# 150309_AriloRX_REV3_1_0.net
KiCad netlist of a schematic drawn in EAGLE
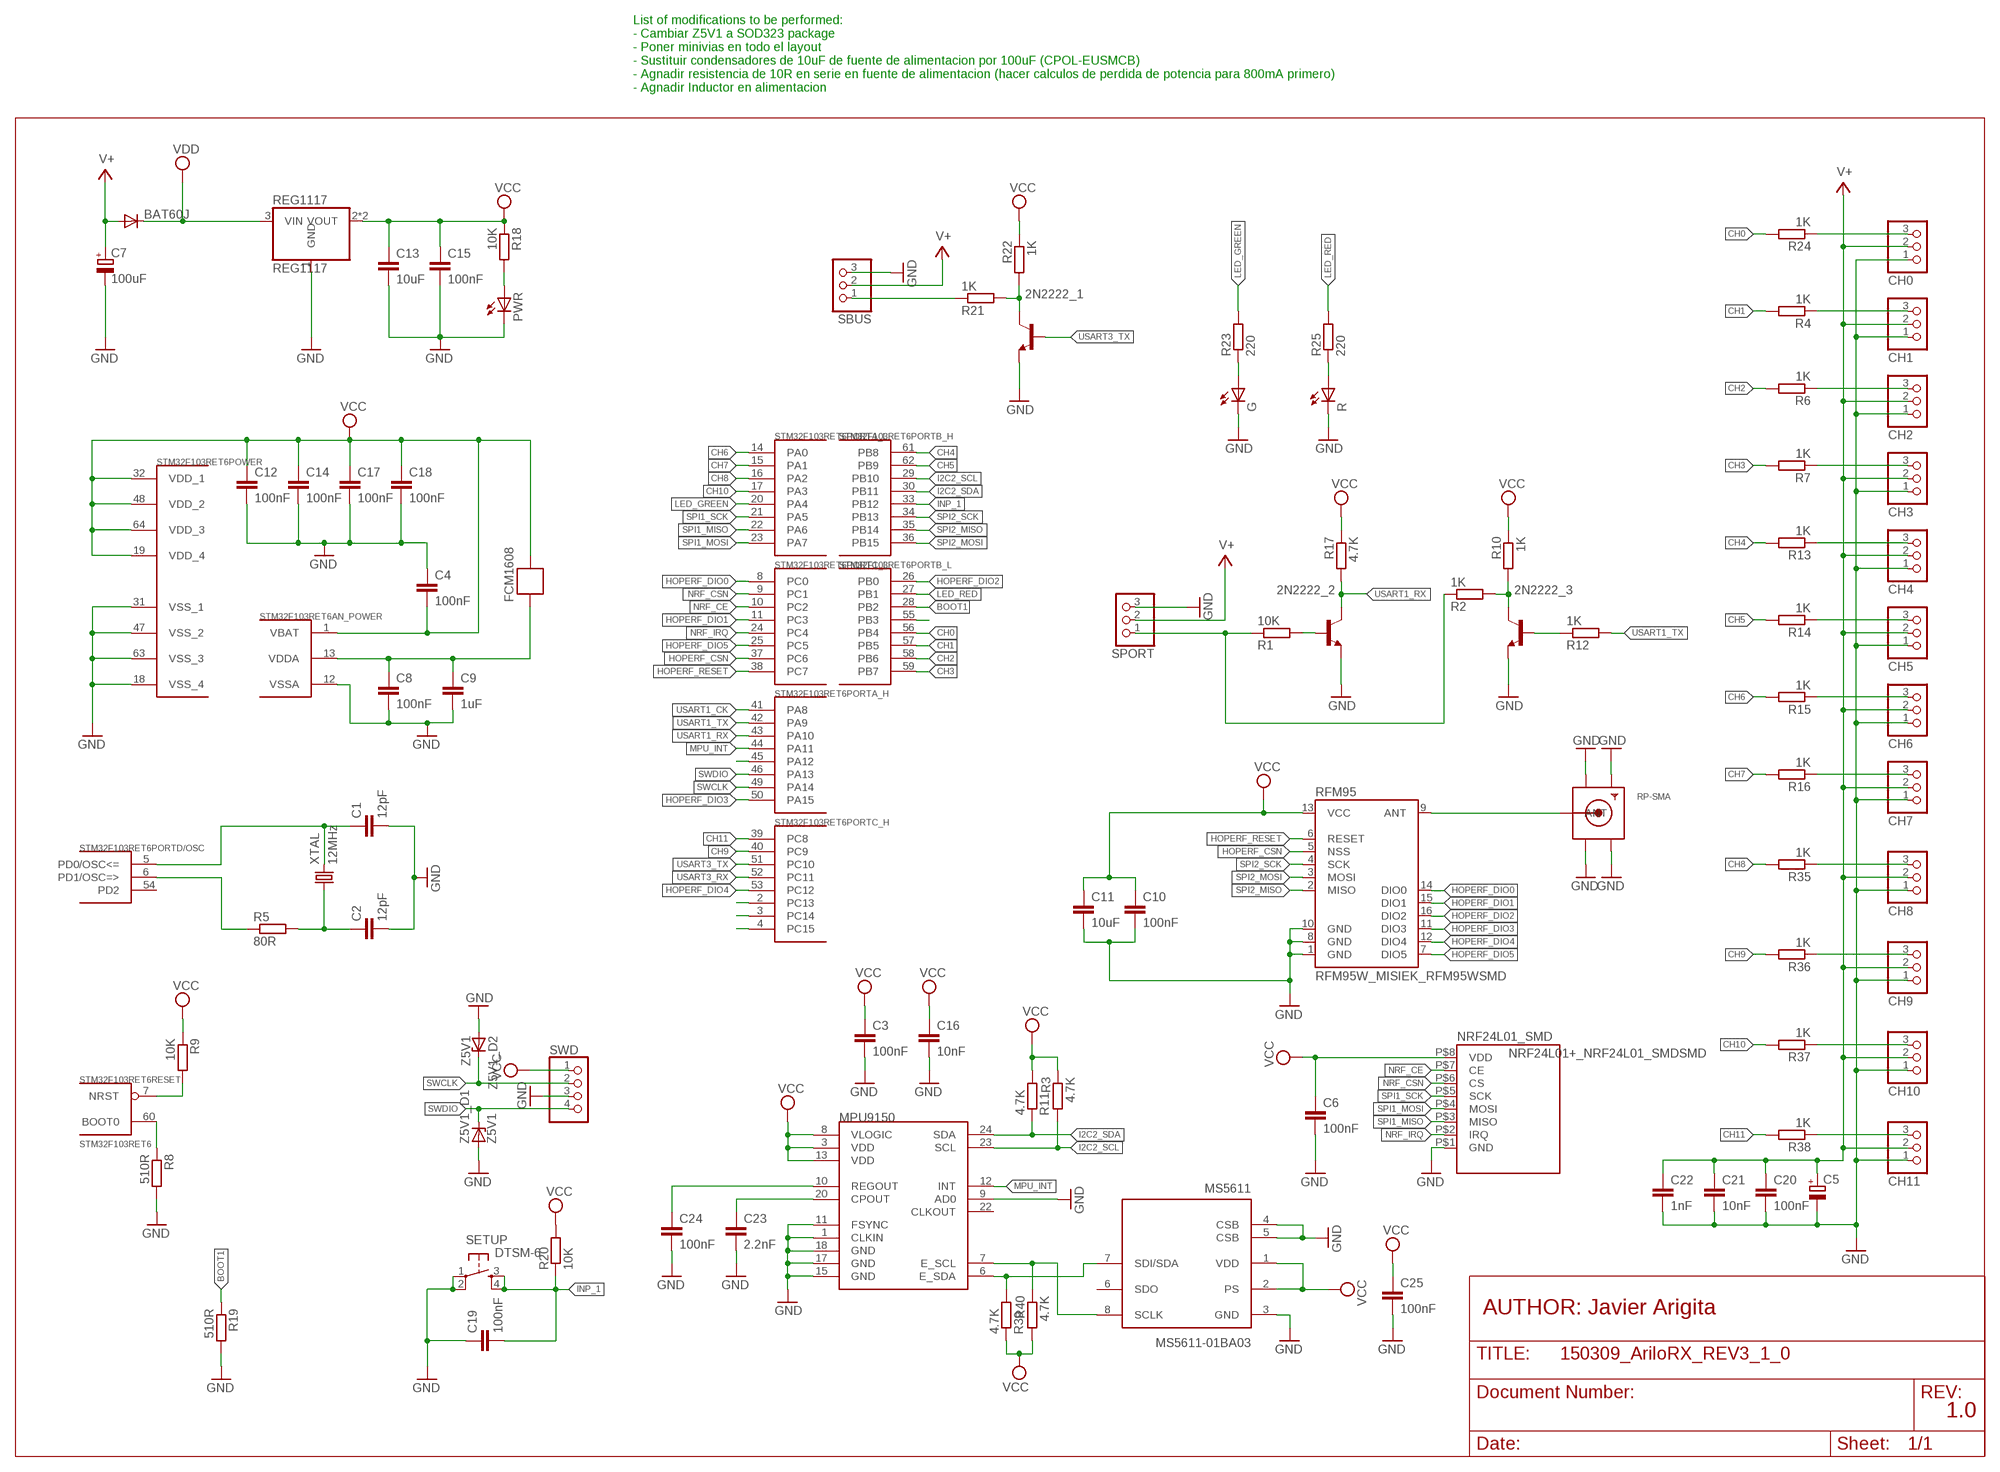
[diagram p0: schematic, sheet 1]

(export (version "E")
  (design (tool "Eeschema 10.0.6"))
  (components
    (comp (ref "2N2222_1")
      (value "MMBT2222ALT1-NPN-SOT23-BEC")
      (footprint "eagle-import:SOT23-BEC")
      (libsource (lib "eagle-import") (part "-NPN-SOT23-BECMMBT2222ALT1"))
    )
    (comp (ref "2N2222_2")
      (value "MMBT2222ALT1-NPN-SOT23-BEC")
      (footprint "eagle-import:SOT23-BEC")
      (libsource (lib "eagle-import") (part "-NPN-SOT23-BECMMBT2222ALT1"))
    )
    (comp (ref "2N2222_3")
      (value "MMBT2222ALT1-NPN-SOT23-BEC")
      (footprint "eagle-import:SOT23-BEC")
      (libsource (lib "eagle-import") (part "-NPN-SOT23-BECMMBT2222ALT1"))
    )
    (comp (ref "BAT60J")
      (value "DIODE-SOD323-R")
      (footprint "eagle-import:SOD323-R")
      (libsource (lib "eagle-import") (part "DIODE-SOD323-R"))
    )
    (comp (ref "C1")
      (value "12pF")
      (footprint "eagle-import:RESISTOR_C0603")
      (libsource (lib "eagle-import") (part "RESISTOR_C-EUC0603"))
    )
    (comp (ref "C2")
      (value "12pF")
      (footprint "eagle-import:RESISTOR_C0603")
      (libsource (lib "eagle-import") (part "RESISTOR_C-EUC0603"))
    )
    (comp (ref "C3")
      (value "100nF")
      (footprint "eagle-import:RESISTOR_C0603")
      (libsource (lib "eagle-import") (part "RESISTOR_C-EUC0603"))
    )
    (comp (ref "C4")
      (value "100nF")
      (footprint "eagle-import:RESISTOR_C0603")
      (libsource (lib "eagle-import") (part "RESISTOR_C-EUC0603"))
    )
    (comp (ref "C5")
      (value "CPOL-EUSMCB")
      (footprint "eagle-import:SMC_B")
      (libsource (lib "eagle-import") (part "CPOL-EUSMCB"))
    )
    (comp (ref "C6")
      (value "100nF")
      (footprint "eagle-import:RESISTOR_C0603")
      (libsource (lib "eagle-import") (part "RESISTOR_C-EUC0603"))
    )
    (comp (ref "C7")
      (value "100uF")
      (footprint "eagle-import:SMC_B")
      (libsource (lib "eagle-import") (part "CPOL-EUSMCB"))
    )
    (comp (ref "C8")
      (value "100nF")
      (footprint "eagle-import:RESISTOR_C0603")
      (libsource (lib "eagle-import") (part "RESISTOR_C-EUC0603"))
    )
    (comp (ref "C9")
      (value "1uF")
      (footprint "eagle-import:RESISTOR_C0603")
      (libsource (lib "eagle-import") (part "RESISTOR_C-EUC0603"))
    )
    (comp (ref "C10")
      (value "100nF")
      (footprint "eagle-import:RESISTOR_C0603")
      (libsource (lib "eagle-import") (part "RESISTOR_C-EUC0603"))
    )
    (comp (ref "C11")
      (value "10uF")
      (footprint "eagle-import:RESISTOR_C3216")
      (libsource (lib "eagle-import") (part "RESISTOR_C-EUC3216"))
    )
    (comp (ref "C12")
      (value "100nF")
      (footprint "eagle-import:RESISTOR_C0603")
      (libsource (lib "eagle-import") (part "RESISTOR_C-EUC0603"))
    )
    (comp (ref "C13")
      (value "10uF")
      (footprint "eagle-import:RESISTOR_C3216")
      (libsource (lib "eagle-import") (part "RESISTOR_C-EUC3216"))
    )
    (comp (ref "C14")
      (value "100nF")
      (footprint "eagle-import:RESISTOR_C0603")
      (libsource (lib "eagle-import") (part "RESISTOR_C-EUC0603"))
    )
    (comp (ref "C15")
      (value "100nF")
      (footprint "eagle-import:RESISTOR_C0603")
      (libsource (lib "eagle-import") (part "RESISTOR_C-EUC0603"))
    )
    (comp (ref "C16")
      (value "10nF")
      (footprint "eagle-import:RESISTOR_C0603")
      (libsource (lib "eagle-import") (part "RESISTOR_C-EUC0603"))
    )
    (comp (ref "C17")
      (value "100nF")
      (footprint "eagle-import:RESISTOR_C0603")
      (libsource (lib "eagle-import") (part "RESISTOR_C-EUC0603"))
    )
    (comp (ref "C18")
      (value "100nF")
      (footprint "eagle-import:RESISTOR_C0603")
      (libsource (lib "eagle-import") (part "RESISTOR_C-EUC0603"))
    )
    (comp (ref "C19")
      (value "100nF")
      (footprint "eagle-import:RESISTOR_C0603")
      (libsource (lib "eagle-import") (part "RESISTOR_C-EUC0603"))
    )
    (comp (ref "C20")
      (value "100nF")
      (footprint "eagle-import:RESISTOR_C0603")
      (libsource (lib "eagle-import") (part "RESISTOR_C-EUC0603"))
    )
    (comp (ref "C21")
      (value "10nF")
      (footprint "eagle-import:RESISTOR_C0603")
      (libsource (lib "eagle-import") (part "RESISTOR_C-EUC0603"))
    )
    (comp (ref "C22")
      (value "1nF")
      (footprint "eagle-import:RESISTOR_C0603")
      (libsource (lib "eagle-import") (part "RESISTOR_C-EUC0603"))
    )
    (comp (ref "C23")
      (value "2.2nF")
      (footprint "eagle-import:RESISTOR_C0603")
      (libsource (lib "eagle-import") (part "RESISTOR_C-EUC0603"))
    )
    (comp (ref "C24")
      (value "100nF")
      (footprint "eagle-import:RESISTOR_C0603")
      (libsource (lib "eagle-import") (part "RESISTOR_C-EUC0603"))
    )
    (comp (ref "C25")
      (value "100nF")
      (footprint "eagle-import:RESISTOR_C0603")
      (libsource (lib "eagle-import") (part "RESISTOR_C-EUC0603"))
    )
    (comp (ref "CH0")
      (value "PINHD-1X3")
      (footprint "eagle-import:1X03")
      (libsource (lib "eagle-import") (part "PINHD-1X3"))
    )
    (comp (ref "CH1")
      (value "PINHD-1X3")
      (footprint "eagle-import:1X03")
      (libsource (lib "eagle-import") (part "PINHD-1X3"))
    )
    (comp (ref "CH2")
      (value "PINHD-1X3")
      (footprint "eagle-import:1X03")
      (libsource (lib "eagle-import") (part "PINHD-1X3"))
    )
    (comp (ref "CH3")
      (value "PINHD-1X3")
      (footprint "eagle-import:1X03")
      (libsource (lib "eagle-import") (part "PINHD-1X3"))
    )
    (comp (ref "CH4")
      (value "PINHD-1X3")
      (footprint "eagle-import:1X03")
      (libsource (lib "eagle-import") (part "PINHD-1X3"))
    )
    (comp (ref "CH5")
      (value "PINHD-1X3")
      (footprint "eagle-import:1X03")
      (libsource (lib "eagle-import") (part "PINHD-1X3"))
    )
    (comp (ref "CH6")
      (value "PINHD-1X3")
      (footprint "eagle-import:1X03")
      (libsource (lib "eagle-import") (part "PINHD-1X3"))
    )
    (comp (ref "CH7")
      (value "PINHD-1X3")
      (footprint "eagle-import:1X03")
      (libsource (lib "eagle-import") (part "PINHD-1X3"))
    )
    (comp (ref "CH8")
      (value "PINHD-1X3")
      (footprint "eagle-import:1X03")
      (libsource (lib "eagle-import") (part "PINHD-1X3"))
    )
    (comp (ref "CH9")
      (value "PINHD-1X3")
      (footprint "eagle-import:1X03")
      (libsource (lib "eagle-import") (part "PINHD-1X3"))
    )
    (comp (ref "CH10")
      (value "PINHD-1X3")
      (footprint "eagle-import:1X03")
      (libsource (lib "eagle-import") (part "PINHD-1X3"))
    )
    (comp (ref "CH11")
      (value "PINHD-1X3")
      (footprint "eagle-import:1X03")
      (libsource (lib "eagle-import") (part "PINHD-1X3"))
    )
    (comp (ref "FCM1608")
      (value "FERRITE-BEAD")
      (footprint "eagle-import:R0603")
      (libsource (lib "eagle-import") (part "FERRITE-BEAD"))
    )
    (comp (ref "G")
      (value "LEDCHIP-LED0603")
      (footprint "eagle-import:CHIP-LED0603")
      (libsource (lib "eagle-import") (part "LEDCHIP-LED0603"))
    )
    (comp (ref "MPU9150")
      (value "MPU-9150QFN-24-NP")
      (footprint "eagle-import:QFN-24-NP")
      (libsource (lib "eagle-import") (part "MPU-9150QFN-24-NP"))
    )
    (comp (ref "MS5611")
      (value "MS5611-01BA03")
      (footprint "eagle-import:SON125P300X500X100-8N")
      (libsource (lib "eagle-import") (part "MS5611-01BA03"))
    )
    (comp (ref "NRF24L01_SMD")
      (value "NRF24L01+_NRF24L01_SMDSMD")
      (footprint "eagle-import:NRF24L01+_NRF24L01_SMD")
      (libsource (lib "eagle-import") (part "NRF24L01+_NRF24L01_SMDSMD"))
    )
    (comp (ref "PWR")
      (value "LED_LEDCHIP-LED0603")
      (footprint "eagle-import:LED_CHIP-LED0603")
      (libsource (lib "eagle-import") (part "LED_LEDCHIP-LED0603"))
    )
    (comp (ref "R")
      (value "LEDCHIP-LED0603")
      (footprint "eagle-import:CHIP-LED0603")
      (libsource (lib "eagle-import") (part "LEDCHIP-LED0603"))
    )
    (comp (ref "R1")
      (value "10K")
      (footprint "eagle-import:RCL_R0603")
      (libsource (lib "eagle-import") (part "RCL_R-EU_R0603"))
    )
    (comp (ref "R2")
      (value "1K")
      (footprint "eagle-import:RCL_R0603")
      (libsource (lib "eagle-import") (part "RCL_R-EU_R0603"))
    )
    (comp (ref "R3")
      (value "4.7K")
      (footprint "eagle-import:RCL_R0603")
      (libsource (lib "eagle-import") (part "RCL_R-EU_R0603"))
    )
    (comp (ref "R4")
      (value "1K")
      (footprint "eagle-import:RCL_R0603")
      (libsource (lib "eagle-import") (part "RCL_R-EU_R0603"))
    )
    (comp (ref "R5")
      (value "80R")
      (footprint "eagle-import:RCL_R0603")
      (libsource (lib "eagle-import") (part "RCL_R-EU_R0603"))
    )
    (comp (ref "R6")
      (value "1K")
      (footprint "eagle-import:RCL_R0603")
      (libsource (lib "eagle-import") (part "RCL_R-EU_R0603"))
    )
    (comp (ref "R7")
      (value "1K")
      (footprint "eagle-import:RCL_R0603")
      (libsource (lib "eagle-import") (part "RCL_R-EU_R0603"))
    )
    (comp (ref "R8")
      (value "510R")
      (footprint "eagle-import:RCL_R0603")
      (libsource (lib "eagle-import") (part "RCL_R-EU_R0603"))
    )
    (comp (ref "R9")
      (value "10K")
      (footprint "eagle-import:RCL_R0603")
      (libsource (lib "eagle-import") (part "RCL_R-EU_R0603"))
    )
    (comp (ref "R10")
      (value "1K")
      (footprint "eagle-import:RCL_R0603")
      (libsource (lib "eagle-import") (part "RCL_R-EU_R0603"))
    )
    (comp (ref "R11")
      (value "4.7K")
      (footprint "eagle-import:RCL_R0603")
      (libsource (lib "eagle-import") (part "RCL_R-EU_R0603"))
    )
    (comp (ref "R12")
      (value "1K")
      (footprint "eagle-import:RCL_R0603")
      (libsource (lib "eagle-import") (part "RCL_R-EU_R0603"))
    )
    (comp (ref "R13")
      (value "1K")
      (footprint "eagle-import:RCL_R0603")
      (libsource (lib "eagle-import") (part "RCL_R-EU_R0603"))
    )
    (comp (ref "R14")
      (value "1K")
      (footprint "eagle-import:RCL_R0603")
      (libsource (lib "eagle-import") (part "RCL_R-EU_R0603"))
    )
    (comp (ref "R15")
      (value "1K")
      (footprint "eagle-import:RCL_R0603")
      (libsource (lib "eagle-import") (part "RCL_R-EU_R0603"))
    )
    (comp (ref "R16")
      (value "1K")
      (footprint "eagle-import:RCL_R0603")
      (libsource (lib "eagle-import") (part "RCL_R-EU_R0603"))
    )
    (comp (ref "R17")
      (value "4.7K")
      (footprint "eagle-import:RCL_R0603")
      (libsource (lib "eagle-import") (part "RCL_R-EU_R0603"))
    )
    (comp (ref "R18")
      (value "10K")
      (footprint "eagle-import:RCL_R0603")
      (libsource (lib "eagle-import") (part "RCL_R-EU_R0603"))
    )
    (comp (ref "R19")
      (value "510R")
      (footprint "eagle-import:RCL_R0603")
      (libsource (lib "eagle-import") (part "RCL_R-EU_R0603"))
    )
    (comp (ref "R20")
      (value "10K")
      (footprint "eagle-import:RCL_R0603")
      (libsource (lib "eagle-import") (part "RCL_R-EU_R0603"))
    )
    (comp (ref "R21")
      (value "1K")
      (footprint "eagle-import:RCL_R0603")
      (libsource (lib "eagle-import") (part "RCL_R-EU_R0603"))
    )
    (comp (ref "R22")
      (value "1K")
      (footprint "eagle-import:RCL_R0603")
      (libsource (lib "eagle-import") (part "RCL_R-EU_R0603"))
    )
    (comp (ref "R23")
      (value "220")
      (footprint "eagle-import:RCL_R0603")
      (libsource (lib "eagle-import") (part "RCL_R-EU_R0603"))
    )
    (comp (ref "R24")
      (value "1K")
      (footprint "eagle-import:RCL_R0603")
      (libsource (lib "eagle-import") (part "RCL_R-EU_R0603"))
    )
    (comp (ref "R25")
      (value "220")
      (footprint "eagle-import:RCL_R0603")
      (libsource (lib "eagle-import") (part "RCL_R-EU_R0603"))
    )
    (comp (ref "R35")
      (value "1K")
      (footprint "eagle-import:RCL_R0603")
      (libsource (lib "eagle-import") (part "RCL_R-EU_R0603"))
    )
    (comp (ref "R36")
      (value "1K")
      (footprint "eagle-import:RCL_R0603")
      (libsource (lib "eagle-import") (part "RCL_R-EU_R0603"))
    )
    (comp (ref "R37")
      (value "1K")
      (footprint "eagle-import:RCL_R0603")
      (libsource (lib "eagle-import") (part "RCL_R-EU_R0603"))
    )
    (comp (ref "R38")
      (value "1K")
      (footprint "eagle-import:RCL_R0603")
      (libsource (lib "eagle-import") (part "RCL_R-EU_R0603"))
    )
    (comp (ref "R39")
      (value "4.7K")
      (footprint "eagle-import:RCL_R0603")
      (libsource (lib "eagle-import") (part "RCL_R-EU_R0603"))
    )
    (comp (ref "R40")
      (value "4.7K")
      (footprint "eagle-import:RCL_R0603")
      (libsource (lib "eagle-import") (part "RCL_R-EU_R0603"))
    )
    (comp (ref "REG1117")
      (value "REG1117")
      (footprint "eagle-import:SOT223")
      (libsource (lib "eagle-import") (part "REG1117"))
    )
    (comp (ref "RFM95")
      (value "RFM95W_MISIEK_RFM95WSMD")
      (footprint "eagle-import:RFM95W_MISIEK_RFM95W_SMD")
      (libsource (lib "eagle-import") (part "RFM95W_MISIEK_RFM95WSMD"))
    )
    (comp (ref "RP-SMA")
      (value "SMACONNECTOR_EDGE")
      (footprint "eagle-import:SMA_EDGELAUNCH")
      (libsource (lib "eagle-import") (part "SMACONNECTOR_EDGE"))
    )
    (comp (ref "SBUS")
      (value "PINHD-1X3")
      (footprint "eagle-import:1X03")
      (libsource (lib "eagle-import") (part "PINHD-1X3"))
    )
    (comp (ref "SETUP")
      (value "DTSM-6")
      (footprint "eagle-import:DTSM-6")
      (libsource (lib "eagle-import") (part "DTSM-6"))
    )
    (comp (ref "SPORT")
      (value "PINHD-1X3")
      (footprint "eagle-import:1X03")
      (libsource (lib "eagle-import") (part "PINHD-1X3"))
    )
    (comp (ref "STM32F103RET6")
      (value "STM32F103RET6")
      (footprint "eagle-import:TQFP64")
      (libsource (lib "eagle-import") (part "STM32F10XRXT6"))
    )
    (comp (ref "SWD")
      (value "PINHD-1X4")
      (footprint "eagle-import:1X04")
      (libsource (lib "eagle-import") (part "PINHD-1X4"))
    )
    (comp (ref "XTAL")
      (value "12MHz")
      (footprint "eagle-import:CRYSTAL-SMD-5X3")
      (libsource (lib "eagle-import") (part "CRYSTAL5X3"))
    )
    (comp (ref "Z5V1_D1")
      (value "Z5V1")
      (footprint "eagle-import:SOD80C")
      (libsource (lib "eagle-import") (part "ZENER-DIODESOD80C"))
    )
    (comp (ref "Z5V1_D2")
      (value "Z5V1")
      (footprint "eagle-import:SOD80C")
      (libsource (lib "eagle-import") (part "ZENER-DIODESOD80C"))
    )
  )
  (nets
    (net (code "1") (name "BOOT1") (class "Default")
      (node (ref "R19") (pin "1") (pinfunction "1_1") (pintype "passive"))
      (node (ref "STM32F103RET6") (pin "28") (pinfunction "PB2_28") (pintype "bidirectional"))
    )
    (net (code "2") (name "CH0") (class "Default")
      (node (ref "R24") (pin "2") (pinfunction "2_2") (pintype "passive"))
      (node (ref "STM32F103RET6") (pin "56") (pinfunction "PB4_56") (pintype "bidirectional"))
    )
    (net (code "3") (name "CH1") (class "Default")
      (node (ref "R4") (pin "2") (pinfunction "2_2") (pintype "passive"))
      (node (ref "STM32F103RET6") (pin "57") (pinfunction "PB5_57") (pintype "bidirectional"))
    )
    (net (code "4") (name "CH2") (class "Default")
      (node (ref "R6") (pin "2") (pinfunction "2_2") (pintype "passive"))
      (node (ref "STM32F103RET6") (pin "58") (pinfunction "PB6_58") (pintype "bidirectional"))
    )
    (net (code "5") (name "CH3") (class "Default")
      (node (ref "R7") (pin "2") (pinfunction "2_2") (pintype "passive"))
      (node (ref "STM32F103RET6") (pin "59") (pinfunction "PB7_59") (pintype "bidirectional"))
    )
    (net (code "6") (name "CH4") (class "Default")
      (node (ref "R13") (pin "2") (pinfunction "2_2") (pintype "passive"))
      (node (ref "STM32F103RET6") (pin "61") (pinfunction "PB8_61") (pintype "bidirectional"))
    )
    (net (code "7") (name "CH5") (class "Default")
      (node (ref "R14") (pin "2") (pinfunction "2_2") (pintype "passive"))
      (node (ref "STM32F103RET6") (pin "62") (pinfunction "PB9_62") (pintype "bidirectional"))
    )
    (net (code "8") (name "CH6") (class "Default")
      (node (ref "R15") (pin "2") (pinfunction "2_2") (pintype "passive"))
      (node (ref "STM32F103RET6") (pin "14") (pinfunction "PA0_14") (pintype "bidirectional"))
    )
    (net (code "9") (name "CH7") (class "Default")
      (node (ref "R16") (pin "2") (pinfunction "2_2") (pintype "passive"))
      (node (ref "STM32F103RET6") (pin "15") (pinfunction "PA1_15") (pintype "bidirectional"))
    )
    (net (code "10") (name "CH8") (class "Default")
      (node (ref "R35") (pin "2") (pinfunction "2_2") (pintype "passive"))
      (node (ref "STM32F103RET6") (pin "16") (pinfunction "PA2_16") (pintype "bidirectional"))
    )
    (net (code "11") (name "CH9") (class "Default")
      (node (ref "R36") (pin "2") (pinfunction "2_2") (pintype "passive"))
      (node (ref "STM32F103RET6") (pin "40") (pinfunction "PC9_40") (pintype "bidirectional"))
    )
    (net (code "12") (name "CH10") (class "Default")
      (node (ref "R37") (pin "2") (pinfunction "2_2") (pintype "passive"))
      (node (ref "STM32F103RET6") (pin "17") (pinfunction "PA3_17") (pintype "bidirectional"))
    )
    (net (code "13") (name "CH11") (class "Default")
      (node (ref "R38") (pin "2") (pinfunction "2_2") (pintype "passive"))
      (node (ref "STM32F103RET6") (pin "39") (pinfunction "PC8_39") (pintype "bidirectional"))
    )
    (net (code "14") (name "GND") (class "Default")
      (node (ref "2N2222_1") (pin "E") (pinfunction "E_E") (pintype "passive"))
      (node (ref "2N2222_2") (pin "E") (pinfunction "E_E") (pintype "passive"))
      (node (ref "2N2222_3") (pin "E") (pinfunction "E_E") (pintype "passive"))
      (node (ref "C1") (pin "2") (pinfunction "2_2") (pintype "passive"))
      (node (ref "C10") (pin "2") (pinfunction "2_2") (pintype "passive"))
      (node (ref "C11") (pin "2") (pinfunction "2_2") (pintype "passive"))
      (node (ref "C12") (pin "2") (pinfunction "2_2") (pintype "passive"))
      (node (ref "C13") (pin "2") (pinfunction "2_2") (pintype "passive"))
      (node (ref "C14") (pin "2") (pinfunction "2_2") (pintype "passive"))
      (node (ref "C15") (pin "2") (pinfunction "2_2") (pintype "passive"))
      (node (ref "C16") (pin "2") (pinfunction "2_2") (pintype "passive"))
      (node (ref "C17") (pin "2") (pinfunction "2_2") (pintype "passive"))
      (node (ref "C18") (pin "2") (pinfunction "2_2") (pintype "passive"))
      (node (ref "C19") (pin "1") (pinfunction "1_1") (pintype "passive"))
      (node (ref "C2") (pin "2") (pinfunction "2_2") (pintype "passive"))
      (node (ref "C20") (pin "2") (pinfunction "2_2") (pintype "passive"))
      (node (ref "C21") (pin "2") (pinfunction "2_2") (pintype "passive"))
      (node (ref "C22") (pin "2") (pinfunction "2_2") (pintype "passive"))
      (node (ref "C23") (pin "2") (pinfunction "2_2") (pintype "passive"))
      (node (ref "C24") (pin "2") (pinfunction "2_2") (pintype "passive"))
      (node (ref "C25") (pin "2") (pinfunction "2_2") (pintype "passive"))
      (node (ref "C3") (pin "2") (pinfunction "2_2") (pintype "passive"))
      (node (ref "C4") (pin "1") (pinfunction "1_1") (pintype "passive"))
      (node (ref "C5") (pin "-") (pinfunction "-_-") (pintype "passive"))
      (node (ref "C6") (pin "2") (pinfunction "2_2") (pintype "passive"))
      (node (ref "C7") (pin "-") (pinfunction "-_-") (pintype "passive"))
      (node (ref "C8") (pin "2") (pinfunction "2_2") (pintype "passive"))
      (node (ref "C9") (pin "2") (pinfunction "2_2") (pintype "passive"))
      (node (ref "CH0") (pin "1") (pinfunction "1_1") (pintype "passive"))
      (node (ref "CH1") (pin "1") (pinfunction "1_1") (pintype "passive"))
      (node (ref "CH10") (pin "1") (pinfunction "1_1") (pintype "passive"))
      (node (ref "CH11") (pin "1") (pinfunction "1_1") (pintype "passive"))
      (node (ref "CH2") (pin "1") (pinfunction "1_1") (pintype "passive"))
      (node (ref "CH3") (pin "1") (pinfunction "1_1") (pintype "passive"))
      (node (ref "CH4") (pin "1") (pinfunction "1_1") (pintype "passive"))
      (node (ref "CH5") (pin "1") (pinfunction "1_1") (pintype "passive"))
      (node (ref "CH6") (pin "1") (pinfunction "1_1") (pintype "passive"))
      (node (ref "CH7") (pin "1") (pinfunction "1_1") (pintype "passive"))
      (node (ref "CH8") (pin "1") (pinfunction "1_1") (pintype "passive"))
      (node (ref "CH9") (pin "1") (pinfunction "1_1") (pintype "passive"))
      (node (ref "G") (pin "C") (pinfunction "C_C") (pintype "passive"))
      (node (ref "MPU9150") (pin "1") (pinfunction "CLKIN_1") (pintype "bidirectional"))
      (node (ref "MPU9150") (pin "11") (pinfunction "FSYNC_11") (pintype "bidirectional"))
      (node (ref "MPU9150") (pin "15") (pinfunction "GND_15") (pintype "bidirectional"))
      (node (ref "MPU9150") (pin "17") (pinfunction "GND_17") (pintype "bidirectional"))
      (node (ref "MPU9150") (pin "18") (pinfunction "GND_18") (pintype "bidirectional"))
      (node (ref "MPU9150") (pin "9") (pinfunction "AD0_9") (pintype "bidirectional"))
      (node (ref "MS5611") (pin "3") (pinfunction "GND_3") (pintype "power_in"))
      (node (ref "MS5611") (pin "4") (pinfunction "CSB_4") (pintype "input"))
      (node (ref "MS5611") (pin "5") (pinfunction "CSB_5") (pintype "input"))
      (node (ref "NRF24L01_SMD") (pin "P$1") (pinfunction "GND_P$1") (pintype "power_in"))
      (node (ref "PWR") (pin "C") (pinfunction "C_C") (pintype "passive"))
      (node (ref "R") (pin "C") (pinfunction "C_C") (pintype "passive"))
      (node (ref "R19") (pin "2") (pinfunction "2_2") (pintype "passive"))
      (node (ref "R8") (pin "2") (pinfunction "2_2") (pintype "passive"))
      (node (ref "REG1117") (pin "1") (pinfunction "GND_1") (pintype "power_in"))
      (node (ref "RFM95") (pin "1") (pinfunction "GND_1") (pintype "power_in"))
      (node (ref "RFM95") (pin "10") (pinfunction "GND_10") (pintype "power_in"))
      (node (ref "RFM95") (pin "8") (pinfunction "GND_8") (pintype "power_in"))
      (node (ref "RP-SMA") (pin "GND@1") (pinfunction "GND4_GND@1") (pintype "power_in"))
      (node (ref "RP-SMA") (pin "GND@2") (pinfunction "GND3_GND@2") (pintype "power_in"))
      (node (ref "RP-SMA") (pin "GND@3") (pinfunction "GND2_GND@3") (pintype "power_in"))
      (node (ref "RP-SMA") (pin "GND@4") (pinfunction "GND1_GND@4") (pintype "power_in"))
      (node (ref "SBUS") (pin "3") (pinfunction "3_3") (pintype "passive"))
      (node (ref "SETUP") (pin "1") (pinfunction "1_1") (pintype "passive"))
      (node (ref "SETUP") (pin "2") (pinfunction "2_2") (pintype "passive"))
      (node (ref "SPORT") (pin "3") (pinfunction "3_3") (pintype "passive"))
      (node (ref "STM32F103RET6") (pin "12") (pinfunction "VSSA_12") (pintype "power_in"))
      (node (ref "STM32F103RET6") (pin "18") (pinfunction "VSS_4_18") (pintype "power_in"))
      (node (ref "STM32F103RET6") (pin "31") (pinfunction "VSS_1_31") (pintype "power_in"))
      (node (ref "STM32F103RET6") (pin "47") (pinfunction "VSS_2_47") (pintype "power_in"))
      (node (ref "STM32F103RET6") (pin "63") (pinfunction "VSS_3_63") (pintype "power_in"))
      (node (ref "SWD") (pin "3") (pinfunction "3_3") (pintype "passive"))
      (node (ref "Z5V1_D1") (pin "A") (pinfunction "A_A") (pintype "passive"))
      (node (ref "Z5V1_D2") (pin "A") (pinfunction "A_A") (pintype "passive"))
    )
    (net (code "15") (name "HOPERF_CSN") (class "Default")
      (node (ref "RFM95") (pin "5") (pinfunction "NSS_5") (pintype "input"))
      (node (ref "STM32F103RET6") (pin "37") (pinfunction "PC6_37") (pintype "bidirectional"))
    )
    (net (code "16") (name "HOPERF_DIO0") (class "Default")
      (node (ref "RFM95") (pin "14") (pinfunction "DIO0_14") (pintype "input"))
      (node (ref "STM32F103RET6") (pin "8") (pinfunction "PC0_8") (pintype "bidirectional"))
    )
    (net (code "17") (name "HOPERF_DIO1") (class "Default")
      (node (ref "RFM95") (pin "15") (pinfunction "DIO1_15") (pintype "input"))
      (node (ref "STM32F103RET6") (pin "11") (pinfunction "PC3_11") (pintype "bidirectional"))
    )
    (net (code "18") (name "HOPERF_DIO2") (class "Default")
      (node (ref "RFM95") (pin "16") (pinfunction "DIO2_16") (pintype "input"))
      (node (ref "STM32F103RET6") (pin "26") (pinfunction "PB0_26") (pintype "bidirectional"))
    )
    (net (code "19") (name "HOPERF_DIO3") (class "Default")
      (node (ref "RFM95") (pin "11") (pinfunction "DIO3_11") (pintype "bidirectional"))
      (node (ref "STM32F103RET6") (pin "50") (pinfunction "PA15_50") (pintype "bidirectional"))
    )
    (net (code "20") (name "HOPERF_DIO4") (class "Default")
      (node (ref "RFM95") (pin "12") (pinfunction "DIO4_12") (pintype "bidirectional"))
      (node (ref "STM32F103RET6") (pin "53") (pinfunction "PC12_53") (pintype "bidirectional"))
    )
    (net (code "21") (name "HOPERF_DIO5") (class "Default")
      (node (ref "RFM95") (pin "7") (pinfunction "DIO5_7") (pintype "bidirectional"))
      (node (ref "STM32F103RET6") (pin "25") (pinfunction "PC5_25") (pintype "bidirectional"))
    )
    (net (code "22") (name "HOPERF_RESET") (class "Default")
      (node (ref "RFM95") (pin "6") (pinfunction "RESET_6") (pintype "output"))
      (node (ref "STM32F103RET6") (pin "38") (pinfunction "PC7_38") (pintype "bidirectional"))
    )
    (net (code "23") (name "I2C2_SCL") (class "Default")
      (node (ref "MPU9150") (pin "23") (pinfunction "SCL_23") (pintype "bidirectional"))
      (node (ref "R3") (pin "2") (pinfunction "2_2") (pintype "passive"))
      (node (ref "STM32F103RET6") (pin "29") (pinfunction "PB10_29") (pintype "bidirectional"))
    )
    (net (code "24") (name "I2C2_SDA") (class "Default")
      (node (ref "MPU9150") (pin "24") (pinfunction "SDA_24") (pintype "bidirectional"))
      (node (ref "R11") (pin "1") (pinfunction "1_1") (pintype "passive"))
      (node (ref "STM32F103RET6") (pin "30") (pinfunction "PB11_30") (pintype "bidirectional"))
    )
    (net (code "25") (name "INP_1") (class "Default")
      (node (ref "C19") (pin "2") (pinfunction "2_2") (pintype "passive"))
      (node (ref "R20") (pin "1") (pinfunction "1_1") (pintype "passive"))
      (node (ref "SETUP") (pin "3") (pinfunction "3_3") (pintype "passive"))
      (node (ref "SETUP") (pin "4") (pinfunction "4_4") (pintype "passive"))
      (node (ref "STM32F103RET6") (pin "33") (pinfunction "PB12_33") (pintype "bidirectional"))
    )
    (net (code "26") (name "LED_GREEN") (class "Default")
      (node (ref "R23") (pin "2") (pinfunction "2_2") (pintype "passive"))
      (node (ref "STM32F103RET6") (pin "20") (pinfunction "PA4_20") (pintype "bidirectional"))
    )
    (net (code "27") (name "LED_RED") (class "Default")
      (node (ref "R25") (pin "2") (pinfunction "2_2") (pintype "passive"))
      (node (ref "STM32F103RET6") (pin "27") (pinfunction "PB1_27") (pintype "bidirectional"))
    )
    (net (code "28") (name "MPU_INT") (class "Default")
      (node (ref "MPU9150") (pin "12") (pinfunction "INT_12") (pintype "bidirectional"))
      (node (ref "STM32F103RET6") (pin "44") (pinfunction "PA11_44") (pintype "bidirectional"))
    )
    (net (code "29") (name "NRF_CE") (class "Default")
      (node (ref "NRF24L01_SMD") (pin "P$7") (pinfunction "CE_P$7") (pintype "input"))
      (node (ref "STM32F103RET6") (pin "10") (pinfunction "PC2_10") (pintype "bidirectional"))
    )
    (net (code "30") (name "NRF_CSN") (class "Default")
      (node (ref "NRF24L01_SMD") (pin "P$6") (pinfunction "CS_P$6") (pintype "input"))
      (node (ref "STM32F103RET6") (pin "9") (pinfunction "PC1_9") (pintype "bidirectional"))
    )
    (net (code "31") (name "NRF_IRQ") (class "Default")
      (node (ref "NRF24L01_SMD") (pin "P$2") (pinfunction "IRQ_P$2") (pintype "output"))
      (node (ref "STM32F103RET6") (pin "24") (pinfunction "PC4_24") (pintype "bidirectional"))
    )
    (net (code "32") (name "Net-(2N2222_1-PadC)") (class "Default")
      (node (ref "2N2222_1") (pin "C") (pinfunction "C_C") (pintype "passive"))
      (node (ref "R21") (pin "2") (pinfunction "2_2") (pintype "passive"))
      (node (ref "R22") (pin "2") (pinfunction "2_2") (pintype "passive"))
    )
    (net (code "33") (name "Net-(2N2222_2-PadB)") (class "Default")
      (node (ref "2N2222_2") (pin "B") (pinfunction "B_B") (pintype "passive"))
      (node (ref "R1") (pin "2") (pinfunction "2_2") (pintype "passive"))
    )
    (net (code "34") (name "Net-(2N2222_3-PadB)") (class "Default")
      (node (ref "2N2222_3") (pin "B") (pinfunction "B_B") (pintype "passive"))
      (node (ref "R12") (pin "1") (pinfunction "1_1") (pintype "passive"))
    )
    (net (code "35") (name "Net-(2N2222_3-PadC)") (class "Default")
      (node (ref "2N2222_3") (pin "C") (pinfunction "C_C") (pintype "passive"))
      (node (ref "R10") (pin "2") (pinfunction "2_2") (pintype "passive"))
      (node (ref "R2") (pin "2") (pinfunction "2_2") (pintype "passive"))
    )
    (net (code "36") (name "Net-(C2-Pad1)") (class "Default")
      (node (ref "C2") (pin "1") (pinfunction "1_1") (pintype "passive"))
      (node (ref "R5") (pin "2") (pinfunction "2_2") (pintype "passive"))
      (node (ref "XTAL") (pin "1") (pinfunction "1_1") (pintype "passive"))
    )
    (net (code "37") (name "Net-(CH0-Pad3)") (class "Default")
      (node (ref "CH0") (pin "3") (pinfunction "3_3") (pintype "passive"))
      (node (ref "R24") (pin "1") (pinfunction "1_1") (pintype "passive"))
    )
    (net (code "38") (name "Net-(CH1-Pad3)") (class "Default")
      (node (ref "CH1") (pin "3") (pinfunction "3_3") (pintype "passive"))
      (node (ref "R4") (pin "1") (pinfunction "1_1") (pintype "passive"))
    )
    (net (code "39") (name "Net-(CH2-Pad3)") (class "Default")
      (node (ref "CH2") (pin "3") (pinfunction "3_3") (pintype "passive"))
      (node (ref "R6") (pin "1") (pinfunction "1_1") (pintype "passive"))
    )
    (net (code "40") (name "Net-(CH3-Pad3)") (class "Default")
      (node (ref "CH3") (pin "3") (pinfunction "3_3") (pintype "passive"))
      (node (ref "R7") (pin "1") (pinfunction "1_1") (pintype "passive"))
    )
    (net (code "41") (name "Net-(CH4-Pad3)") (class "Default")
      (node (ref "CH4") (pin "3") (pinfunction "3_3") (pintype "passive"))
      (node (ref "R13") (pin "1") (pinfunction "1_1") (pintype "passive"))
    )
    (net (code "42") (name "Net-(CH5-Pad3)") (class "Default")
      (node (ref "CH5") (pin "3") (pinfunction "3_3") (pintype "passive"))
      (node (ref "R14") (pin "1") (pinfunction "1_1") (pintype "passive"))
    )
    (net (code "43") (name "Net-(CH6-Pad3)") (class "Default")
      (node (ref "CH6") (pin "3") (pinfunction "3_3") (pintype "passive"))
      (node (ref "R15") (pin "1") (pinfunction "1_1") (pintype "passive"))
    )
    (net (code "44") (name "Net-(CH7-Pad3)") (class "Default")
      (node (ref "CH7") (pin "3") (pinfunction "3_3") (pintype "passive"))
      (node (ref "R16") (pin "1") (pinfunction "1_1") (pintype "passive"))
    )
    (net (code "45") (name "Net-(CH8-Pad3)") (class "Default")
      (node (ref "CH8") (pin "3") (pinfunction "3_3") (pintype "passive"))
      (node (ref "R35") (pin "1") (pinfunction "1_1") (pintype "passive"))
    )
    (net (code "46") (name "Net-(CH9-Pad3)") (class "Default")
      (node (ref "CH9") (pin "3") (pinfunction "3_3") (pintype "passive"))
      (node (ref "R36") (pin "1") (pinfunction "1_1") (pintype "passive"))
    )
    (net (code "47") (name "Net-(CH10-Pad3)") (class "Default")
      (node (ref "CH10") (pin "3") (pinfunction "3_3") (pintype "passive"))
      (node (ref "R37") (pin "1") (pinfunction "1_1") (pintype "passive"))
    )
    (net (code "48") (name "Net-(CH11-Pad3)") (class "Default")
      (node (ref "CH11") (pin "3") (pinfunction "3_3") (pintype "passive"))
      (node (ref "R38") (pin "1") (pinfunction "1_1") (pintype "passive"))
    )
    (net (code "49") (name "Net-(FCM1608-P$2)") (class "Default")
      (node (ref "C8") (pin "1") (pinfunction "1_1") (pintype "passive"))
      (node (ref "C9") (pin "1") (pinfunction "1_1") (pintype "passive"))
      (node (ref "FCM1608") (pin "2") (pinfunction "P$2_2") (pintype "bidirectional"))
      (node (ref "STM32F103RET6") (pin "13") (pinfunction "VDDA_13") (pintype "power_in"))
    )
    (net (code "50") (name "Net-(G-PadA)") (class "Default")
      (node (ref "G") (pin "A") (pinfunction "A_A") (pintype "passive"))
      (node (ref "R23") (pin "1") (pinfunction "1_1") (pintype "passive"))
    )
    (net (code "51") (name "Net-(MPU9150-CPOUT)") (class "Default")
      (node (ref "C23") (pin "1") (pinfunction "1_1") (pintype "passive"))
      (node (ref "MPU9150") (pin "20") (pinfunction "CPOUT_20") (pintype "bidirectional"))
    )
    (net (code "52") (name "Net-(MPU9150-E_SCL)") (class "Default")
      (node (ref "MPU9150") (pin "7") (pinfunction "E_SCL_7") (pintype "bidirectional"))
      (node (ref "MS5611") (pin "8") (pinfunction "SCLK_8") (pintype "input"))
      (node (ref "R40") (pin "1") (pinfunction "1_1") (pintype "passive"))
    )
    (net (code "53") (name "Net-(MPU9150-E_SDA)") (class "Default")
      (node (ref "MPU9150") (pin "6") (pinfunction "E_SDA_6") (pintype "bidirectional"))
      (node (ref "MS5611") (pin "7") (pinfunction "SDI/SDA_7") (pintype "bidirectional"))
      (node (ref "R39") (pin "2") (pinfunction "2_2") (pintype "passive"))
    )
    (net (code "54") (name "Net-(MPU9150-REGOUT)") (class "Default")
      (node (ref "C24") (pin "1") (pinfunction "1_1") (pintype "passive"))
      (node (ref "MPU9150") (pin "10") (pinfunction "REGOUT_10") (pintype "bidirectional"))
    )
    (net (code "55") (name "Net-(PWR-PadA)") (class "Default")
      (node (ref "PWR") (pin "A") (pinfunction "A_A") (pintype "passive"))
      (node (ref "R18") (pin "2") (pinfunction "2_2") (pintype "passive"))
    )
    (net (code "56") (name "Net-(R-PadA)") (class "Default")
      (node (ref "R") (pin "A") (pinfunction "A_A") (pintype "passive"))
      (node (ref "R25") (pin "1") (pinfunction "1_1") (pintype "passive"))
    )
    (net (code "57") (name "Net-(R1-Pad1)") (class "Default")
      (node (ref "R1") (pin "1") (pinfunction "1_1") (pintype "passive"))
      (node (ref "R2") (pin "1") (pinfunction "1_1") (pintype "passive"))
      (node (ref "SPORT") (pin "1") (pinfunction "1_1") (pintype "passive"))
    )
    (net (code "58") (name "Net-(R21-Pad1)") (class "Default")
      (node (ref "R21") (pin "1") (pinfunction "1_1") (pintype "passive"))
      (node (ref "SBUS") (pin "1") (pinfunction "1_1") (pintype "passive"))
    )
    (net (code "59") (name "Net-(RFM95-ANT)") (class "Default")
      (node (ref "RFM95") (pin "9") (pinfunction "ANT_9") (pintype "bidirectional"))
      (node (ref "RP-SMA") (pin "P") (pinfunction "ANT_P") (pintype "bidirectional"))
    )
    (net (code "60") (name "Net-(STM32F103RET6H-PD0{slash}OSC<=)") (class "Default")
      (node (ref "C1") (pin "1") (pinfunction "1_1") (pintype "passive"))
      (node (ref "STM32F103RET6") (pin "5") (pinfunction "PD0/OSC<=_5") (pintype "bidirectional"))
      (node (ref "XTAL") (pin "3") (pinfunction "2_3") (pintype "passive"))
    )
    (net (code "61") (name "Net-(STM32F103RET6H-PD1{slash}OSC=>)") (class "Default")
      (node (ref "R5") (pin "1") (pinfunction "1_1") (pintype "passive"))
      (node (ref "STM32F103RET6") (pin "6") (pinfunction "PD1/OSC=>_6") (pintype "bidirectional"))
    )
    (net (code "62") (name "Net-(STM32F103RET6J-BOOT0)") (class "Default")
      (node (ref "R8") (pin "1") (pinfunction "1_1") (pintype "passive"))
      (node (ref "STM32F103RET6") (pin "60") (pinfunction "BOOT0_60") (pintype "input"))
    )
    (net (code "63") (name "Net-(STM32F103RET6J-NRST)") (class "Default")
      (node (ref "R9") (pin "2") (pinfunction "2_2") (pintype "passive"))
      (node (ref "STM32F103RET6") (pin "7") (pinfunction "NRST_7") (pintype "input"))
    )
    (net (code "64") (name "SPI1_MISO") (class "Default")
      (node (ref "NRF24L01_SMD") (pin "P$3") (pinfunction "MISO_P$3") (pintype "output"))
      (node (ref "STM32F103RET6") (pin "22") (pinfunction "PA6_22") (pintype "bidirectional"))
    )
    (net (code "65") (name "SPI1_MOSI") (class "Default")
      (node (ref "NRF24L01_SMD") (pin "P$4") (pinfunction "MOSI_P$4") (pintype "input"))
      (node (ref "STM32F103RET6") (pin "23") (pinfunction "PA7_23") (pintype "bidirectional"))
    )
    (net (code "66") (name "SPI1_SCK") (class "Default")
      (node (ref "NRF24L01_SMD") (pin "P$5") (pinfunction "SCK_P$5") (pintype "input"))
      (node (ref "STM32F103RET6") (pin "21") (pinfunction "PA5_21") (pintype "bidirectional"))
    )
    (net (code "67") (name "SPI2_MISO") (class "Default")
      (node (ref "RFM95") (pin "2") (pinfunction "MISO_2") (pintype "output"))
      (node (ref "STM32F103RET6") (pin "35") (pinfunction "PB14_35") (pintype "bidirectional"))
    )
    (net (code "68") (name "SPI2_MOSI") (class "Default")
      (node (ref "RFM95") (pin "3") (pinfunction "MOSI_3") (pintype "input"))
      (node (ref "STM32F103RET6") (pin "36") (pinfunction "PB15_36") (pintype "bidirectional"))
    )
    (net (code "69") (name "SPI2_SCK") (class "Default")
      (node (ref "RFM95") (pin "4") (pinfunction "SCK_4") (pintype "input"))
      (node (ref "STM32F103RET6") (pin "34") (pinfunction "PB13_34") (pintype "bidirectional"))
    )
    (net (code "70") (name "SWCLK") (class "Default")
      (node (ref "STM32F103RET6") (pin "49") (pinfunction "PA14_49") (pintype "bidirectional"))
      (node (ref "SWD") (pin "2") (pinfunction "2_2") (pintype "passive"))
      (node (ref "Z5V1_D2") (pin "C") (pinfunction "C_C") (pintype "passive"))
    )
    (net (code "71") (name "SWDIO") (class "Default")
      (node (ref "STM32F103RET6") (pin "46") (pinfunction "PA13_46") (pintype "bidirectional"))
      (node (ref "SWD") (pin "4") (pinfunction "4_4") (pintype "passive"))
      (node (ref "Z5V1_D1") (pin "C") (pinfunction "C_C") (pintype "passive"))
    )
    (net (code "72") (name "USART1_CK") (class "Default")
      (node (ref "STM32F103RET6") (pin "41") (pinfunction "PA8_41") (pintype "bidirectional"))
    )
    (net (code "73") (name "USART1_RX") (class "Default")
      (node (ref "2N2222_2") (pin "C") (pinfunction "C_C") (pintype "passive"))
      (node (ref "R17") (pin "2") (pinfunction "2_2") (pintype "passive"))
      (node (ref "STM32F103RET6") (pin "43") (pinfunction "PA10_43") (pintype "bidirectional"))
    )
    (net (code "74") (name "USART1_TX") (class "Default")
      (node (ref "R12") (pin "2") (pinfunction "2_2") (pintype "passive"))
      (node (ref "STM32F103RET6") (pin "42") (pinfunction "PA9_42") (pintype "bidirectional"))
    )
    (net (code "75") (name "USART3_RX") (class "Default")
      (node (ref "STM32F103RET6") (pin "52") (pinfunction "PC11_52") (pintype "bidirectional"))
    )
    (net (code "76") (name "USART3_TX") (class "Default")
      (node (ref "2N2222_1") (pin "B") (pinfunction "B_B") (pintype "passive"))
      (node (ref "STM32F103RET6") (pin "51") (pinfunction "PC10_51") (pintype "bidirectional"))
    )
    (net (code "77") (name "V+") (class "Default")
      (node (ref "BAT60J") (pin "A") (pinfunction "A_A") (pintype "passive"))
      (node (ref "C20") (pin "1") (pinfunction "1_1") (pintype "passive"))
      (node (ref "C21") (pin "1") (pinfunction "1_1") (pintype "passive"))
      (node (ref "C22") (pin "1") (pinfunction "1_1") (pintype "passive"))
      (node (ref "C5") (pin "+") (pinfunction "+_+") (pintype "passive"))
      (node (ref "C7") (pin "+") (pinfunction "+_+") (pintype "passive"))
      (node (ref "CH0") (pin "2") (pinfunction "2_2") (pintype "passive"))
      (node (ref "CH1") (pin "2") (pinfunction "2_2") (pintype "passive"))
      (node (ref "CH10") (pin "2") (pinfunction "2_2") (pintype "passive"))
      (node (ref "CH11") (pin "2") (pinfunction "2_2") (pintype "passive"))
      (node (ref "CH2") (pin "2") (pinfunction "2_2") (pintype "passive"))
      (node (ref "CH3") (pin "2") (pinfunction "2_2") (pintype "passive"))
      (node (ref "CH4") (pin "2") (pinfunction "2_2") (pintype "passive"))
      (node (ref "CH5") (pin "2") (pinfunction "2_2") (pintype "passive"))
      (node (ref "CH6") (pin "2") (pinfunction "2_2") (pintype "passive"))
      (node (ref "CH7") (pin "2") (pinfunction "2_2") (pintype "passive"))
      (node (ref "CH8") (pin "2") (pinfunction "2_2") (pintype "passive"))
      (node (ref "CH9") (pin "2") (pinfunction "2_2") (pintype "passive"))
      (node (ref "SBUS") (pin "2") (pinfunction "2_2") (pintype "passive"))
      (node (ref "SPORT") (pin "2") (pinfunction "2_2") (pintype "passive"))
    )
    (net (code "78") (name "VCC") (class "Default")
      (node (ref "C10") (pin "1") (pinfunction "1_1") (pintype "passive"))
      (node (ref "C11") (pin "1") (pinfunction "1_1") (pintype "passive"))
      (node (ref "C12") (pin "1") (pinfunction "1_1") (pintype "passive"))
      (node (ref "C13") (pin "1") (pinfunction "1_1") (pintype "passive"))
      (node (ref "C14") (pin "1") (pinfunction "1_1") (pintype "passive"))
      (node (ref "C15") (pin "1") (pinfunction "1_1") (pintype "passive"))
      (node (ref "C16") (pin "1") (pinfunction "1_1") (pintype "passive"))
      (node (ref "C17") (pin "1") (pinfunction "1_1") (pintype "passive"))
      (node (ref "C18") (pin "1") (pinfunction "1_1") (pintype "passive"))
      (node (ref "C25") (pin "1") (pinfunction "1_1") (pintype "passive"))
      (node (ref "C3") (pin "1") (pinfunction "1_1") (pintype "passive"))
      (node (ref "C4") (pin "2") (pinfunction "2_2") (pintype "passive"))
      (node (ref "C6") (pin "1") (pinfunction "1_1") (pintype "passive"))
      (node (ref "FCM1608") (pin "1") (pinfunction "P$1_1") (pintype "bidirectional"))
      (node (ref "MPU9150") (pin "13") (pinfunction "VDD_13") (pintype "bidirectional"))
      (node (ref "MPU9150") (pin "3") (pinfunction "VDD_3") (pintype "bidirectional"))
      (node (ref "MPU9150") (pin "8") (pinfunction "VLOGIC_8") (pintype "bidirectional"))
      (node (ref "MS5611") (pin "1") (pinfunction "VDD_1") (pintype "power_in"))
      (node (ref "MS5611") (pin "2") (pinfunction "PS_2") (pintype "input"))
      (node (ref "NRF24L01_SMD") (pin "P$8") (pinfunction "VDD_P$8") (pintype "bidirectional"))
      (node (ref "R10") (pin "1") (pinfunction "1_1") (pintype "passive"))
      (node (ref "R11") (pin "2") (pinfunction "2_2") (pintype "passive"))
      (node (ref "R17") (pin "1") (pinfunction "1_1") (pintype "passive"))
      (node (ref "R18") (pin "1") (pinfunction "1_1") (pintype "passive"))
      (node (ref "R20") (pin "2") (pinfunction "2_2") (pintype "passive"))
      (node (ref "R22") (pin "1") (pinfunction "1_1") (pintype "passive"))
      (node (ref "R3") (pin "1") (pinfunction "1_1") (pintype "passive"))
      (node (ref "R39") (pin "1") (pinfunction "1_1") (pintype "passive"))
      (node (ref "R40") (pin "2") (pinfunction "2_2") (pintype "passive"))
      (node (ref "R9") (pin "1") (pinfunction "1_1") (pintype "passive"))
      (node (ref "REG1117") (pin "2") (pinfunction "VOUT_2") (pintype "power_in"))
      (node (ref "REG1117") (pin "4") (pinfunction "VOUT_4") (pintype "power_in"))
      (node (ref "RFM95") (pin "13") (pinfunction "VCC_13") (pintype "bidirectional"))
      (node (ref "STM32F103RET6") (pin "1") (pinfunction "VBAT_1") (pintype "power_in"))
      (node (ref "STM32F103RET6") (pin "19") (pinfunction "VDD_4_19") (pintype "power_in"))
      (node (ref "STM32F103RET6") (pin "32") (pinfunction "VDD_1_32") (pintype "power_in"))
      (node (ref "STM32F103RET6") (pin "48") (pinfunction "VDD_2_48") (pintype "power_in"))
      (node (ref "STM32F103RET6") (pin "64") (pinfunction "VDD_3_64") (pintype "power_in"))
      (node (ref "SWD") (pin "1") (pinfunction "1_1") (pintype "passive"))
    )
    (net (code "79") (name "VDD") (class "Default")
      (node (ref "BAT60J") (pin "C") (pinfunction "C_C") (pintype "passive"))
      (node (ref "REG1117") (pin "3") (pinfunction "VIN_3") (pintype "input"))
    )
    (net (code "80") (name "unconnected-(MPU9150-CLKOUT-Pad22)") (class "Default")
      (node (ref "MPU9150") (pin "22") (pinfunction "CLKOUT_22") (pintype "bidirectional"))
    )
    (net (code "81") (name "unconnected-(MS5611-SDO-Pad6)") (class "Default")
      (node (ref "MS5611") (pin "6") (pinfunction "SDO_6") (pintype "output"))
    )
    (net (code "82") (name "unconnected-(STM32F103RET6B-PA12-Pad45)") (class "Default")
      (node (ref "STM32F103RET6") (pin "45") (pinfunction "PA12_45") (pintype "bidirectional"))
    )
    (net (code "83") (name "unconnected-(STM32F103RET6E-PB3-Pad55)") (class "Default")
      (node (ref "STM32F103RET6") (pin "55") (pinfunction "PB3_55") (pintype "bidirectional"))
    )
    (net (code "84") (name "unconnected-(STM32F103RET6F-PC13-Pad2)") (class "Default")
      (node (ref "STM32F103RET6") (pin "2") (pinfunction "PC13_2") (pintype "bidirectional"))
    )
    (net (code "85") (name "unconnected-(STM32F103RET6F-PC14-Pad3)") (class "Default")
      (node (ref "STM32F103RET6") (pin "3") (pinfunction "PC14_3") (pintype "bidirectional"))
    )
    (net (code "86") (name "unconnected-(STM32F103RET6F-PC15-Pad4)") (class "Default")
      (node (ref "STM32F103RET6") (pin "4") (pinfunction "PC15_4") (pintype "bidirectional"))
    )
    (net (code "87") (name "unconnected-(STM32F103RET6H-PD2-Pad54)") (class "Default")
      (node (ref "STM32F103RET6") (pin "54") (pinfunction "PD2_54") (pintype "bidirectional"))
    )
  )
)
